# FCT_connector.net
KiCad netlist of a schematic drawn in Altium Designer
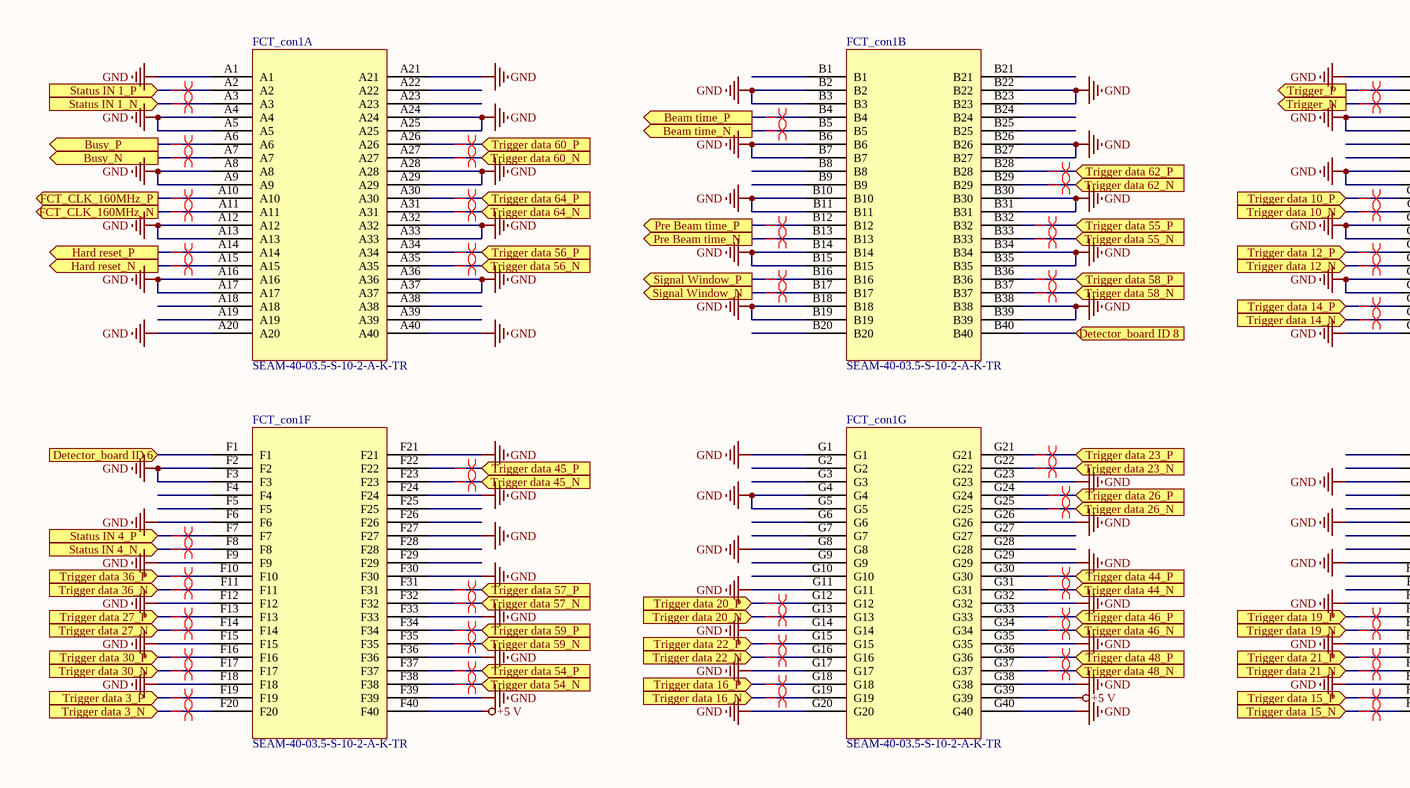
[diagram p0: FCT_connector.SchDoc, left]
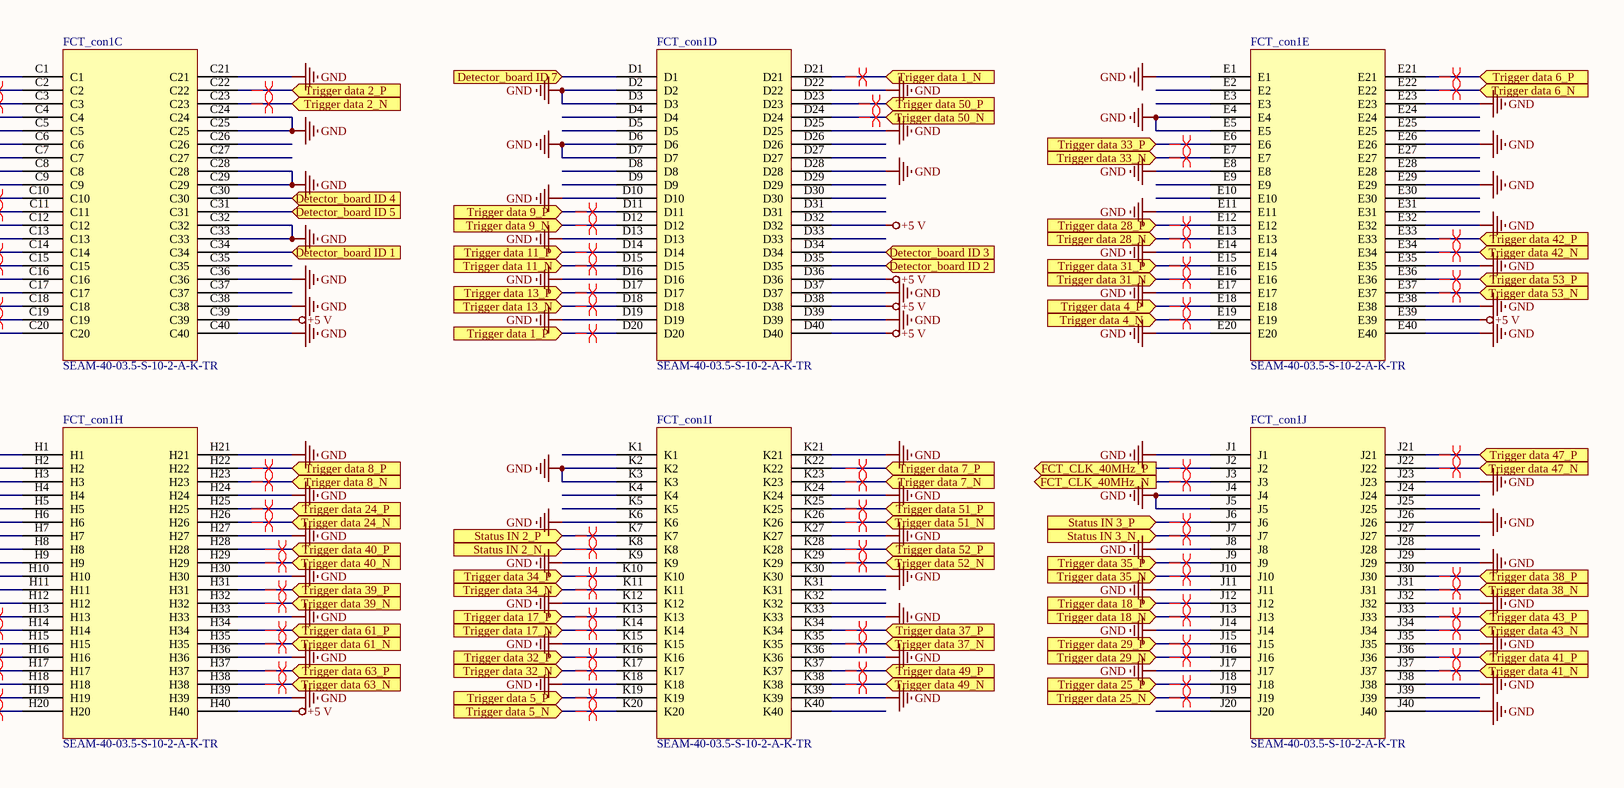
[diagram p1: FCT_connector.SchDoc, right]

(export (version "E")
  (design (tool "Eeschema 10.0.6"))
  (components
    (comp (ref "FCT_con1")
      (value "SEAM-40-03.5-S-10-2-A-K-TR")
      (footprint "SEAM-40-03.5-S-10-2-A-K-TR")
      (libsource (lib "vDevice") (part "SEAM-40-03.5-S-10-2-A-K-TR"))
    )
  )
  (nets
    (net (code "1") (name "+5 V") (class "Default")
      (node (ref "FCT_con1") (pin "C39") (pinfunction "C39_C39") (pintype "passive"))
      (node (ref "FCT_con1") (pin "D32") (pinfunction "D32_D32") (pintype "passive"))
      (node (ref "FCT_con1") (pin "D36") (pinfunction "D36_D36") (pintype "passive"))
      (node (ref "FCT_con1") (pin "D38") (pinfunction "D38_D38") (pintype "passive"))
      (node (ref "FCT_con1") (pin "D40") (pinfunction "D40_D40") (pintype "passive"))
      (node (ref "FCT_con1") (pin "E39") (pinfunction "E39_E39") (pintype "passive"))
      (node (ref "FCT_con1") (pin "F40") (pinfunction "F40_F40") (pintype "passive"))
      (node (ref "FCT_con1") (pin "G39") (pinfunction "G39_G39") (pintype "passive"))
      (node (ref "FCT_con1") (pin "H40") (pinfunction "H40_H40") (pintype "passive"))
    )
    (net (code "2") (name "/Beam time_N") (class "Default")
      (node (ref "FCT_con1") (pin "B5") (pinfunction "B5_B5") (pintype "passive"))
    )
    (net (code "3") (name "/Beam time_P") (class "Default")
      (node (ref "FCT_con1") (pin "B4") (pinfunction "B4_B4") (pintype "passive"))
    )
    (net (code "4") (name "/Busy_N") (class "Default")
      (node (ref "FCT_con1") (pin "A7") (pinfunction "A7_A7") (pintype "passive"))
    )
    (net (code "5") (name "/Busy_P") (class "Default")
      (node (ref "FCT_con1") (pin "A6") (pinfunction "A6_A6") (pintype "passive"))
    )
    (net (code "6") (name "/Detector_board ID 1") (class "Default")
      (node (ref "FCT_con1") (pin "C34") (pinfunction "C34_C34") (pintype "passive"))
    )
    (net (code "7") (name "/Detector_board ID 2") (class "Default")
      (node (ref "FCT_con1") (pin "D35") (pinfunction "D35_D35") (pintype "passive"))
    )
    (net (code "8") (name "/Detector_board ID 3") (class "Default")
      (node (ref "FCT_con1") (pin "D34") (pinfunction "D34_D34") (pintype "passive"))
    )
    (net (code "9") (name "/Detector_board ID 4") (class "Default")
      (node (ref "FCT_con1") (pin "C30") (pinfunction "C30_C30") (pintype "passive"))
    )
    (net (code "10") (name "/Detector_board ID 5") (class "Default")
      (node (ref "FCT_con1") (pin "C31") (pinfunction "C31_C31") (pintype "passive"))
    )
    (net (code "11") (name "/Detector_board ID 6") (class "Default")
      (node (ref "FCT_con1") (pin "F1") (pinfunction "F1_F1") (pintype "passive"))
    )
    (net (code "12") (name "/Detector_board ID 7") (class "Default")
      (node (ref "FCT_con1") (pin "D1") (pinfunction "D1_D1") (pintype "passive"))
    )
    (net (code "13") (name "/Detector_board ID 8") (class "Default")
      (node (ref "FCT_con1") (pin "B40") (pinfunction "B40_B40") (pintype "passive"))
    )
    (net (code "14") (name "/FCT_CLK_40MHz_N") (class "Default")
      (node (ref "FCT_con1") (pin "J3") (pinfunction "J3_J3") (pintype "passive"))
    )
    (net (code "15") (name "/FCT_CLK_40MHz_P") (class "Default")
      (node (ref "FCT_con1") (pin "J2") (pinfunction "J2_J2") (pintype "passive"))
    )
    (net (code "16") (name "/FCT_CLK_160MHz_N") (class "Default")
      (node (ref "FCT_con1") (pin "A11") (pinfunction "A11_A11") (pintype "passive"))
    )
    (net (code "17") (name "/FCT_CLK_160MHz_P") (class "Default")
      (node (ref "FCT_con1") (pin "A10") (pinfunction "A10_A10") (pintype "passive"))
    )
    (net (code "18") (name "/Hard reset_N") (class "Default")
      (node (ref "FCT_con1") (pin "A15") (pinfunction "A15_A15") (pintype "passive"))
    )
    (net (code "19") (name "/Hard reset_P") (class "Default")
      (node (ref "FCT_con1") (pin "A14") (pinfunction "A14_A14") (pintype "passive"))
    )
    (net (code "20") (name "/Pre Beam time_N") (class "Default")
      (node (ref "FCT_con1") (pin "B13") (pinfunction "B13_B13") (pintype "passive"))
    )
    (net (code "21") (name "/Pre Beam time_P") (class "Default")
      (node (ref "FCT_con1") (pin "B12") (pinfunction "B12_B12") (pintype "passive"))
    )
    (net (code "22") (name "/Signal Window_N") (class "Default")
      (node (ref "FCT_con1") (pin "B17") (pinfunction "B17_B17") (pintype "passive"))
    )
    (net (code "23") (name "/Signal Window_P") (class "Default")
      (node (ref "FCT_con1") (pin "B16") (pinfunction "B16_B16") (pintype "passive"))
    )
    (net (code "24") (name "/Status IN 1_N") (class "Default")
      (node (ref "FCT_con1") (pin "A3") (pinfunction "A3_A3") (pintype "passive"))
    )
    (net (code "25") (name "/Status IN 1_P") (class "Default")
      (node (ref "FCT_con1") (pin "A2") (pinfunction "A2_A2") (pintype "passive"))
    )
    (net (code "26") (name "/Status IN 2_N") (class "Default")
      (node (ref "FCT_con1") (pin "K8") (pinfunction "K8_K8") (pintype "passive"))
    )
    (net (code "27") (name "/Status IN 2_P") (class "Default")
      (node (ref "FCT_con1") (pin "K7") (pinfunction "K7_K7") (pintype "passive"))
    )
    (net (code "28") (name "/Status IN 3_N") (class "Default")
      (node (ref "FCT_con1") (pin "J7") (pinfunction "J7_J7") (pintype "passive"))
    )
    (net (code "29") (name "/Status IN 3_P") (class "Default")
      (node (ref "FCT_con1") (pin "J6") (pinfunction "J6_J6") (pintype "passive"))
    )
    (net (code "30") (name "/Status IN 4_N") (class "Default")
      (node (ref "FCT_con1") (pin "F8") (pinfunction "F8_F8") (pintype "passive"))
    )
    (net (code "31") (name "/Status IN 4_P") (class "Default")
      (node (ref "FCT_con1") (pin "F7") (pinfunction "F7_F7") (pintype "passive"))
    )
    (net (code "32") (name "/Trigger data 1_N") (class "Default")
      (node (ref "FCT_con1") (pin "D21") (pinfunction "D21_D21") (pintype "passive"))
    )
    (net (code "33") (name "/Trigger data 1_P") (class "Default")
      (node (ref "FCT_con1") (pin "D20") (pinfunction "D20_D20") (pintype "passive"))
    )
    (net (code "34") (name "/Trigger data 2_N") (class "Default")
      (node (ref "FCT_con1") (pin "C23") (pinfunction "C23_C23") (pintype "passive"))
    )
    (net (code "35") (name "/Trigger data 2_P") (class "Default")
      (node (ref "FCT_con1") (pin "C22") (pinfunction "C22_C22") (pintype "passive"))
    )
    (net (code "36") (name "/Trigger data 3_N") (class "Default")
      (node (ref "FCT_con1") (pin "F20") (pinfunction "F20_F20") (pintype "passive"))
    )
    (net (code "37") (name "/Trigger data 3_P") (class "Default")
      (node (ref "FCT_con1") (pin "F19") (pinfunction "F19_F19") (pintype "passive"))
    )
    (net (code "38") (name "/Trigger data 4_N") (class "Default")
      (node (ref "FCT_con1") (pin "E19") (pinfunction "E19_E19") (pintype "passive"))
    )
    (net (code "39") (name "/Trigger data 4_P") (class "Default")
      (node (ref "FCT_con1") (pin "E18") (pinfunction "E18_E18") (pintype "passive"))
    )
    (net (code "40") (name "/Trigger data 5_N") (class "Default")
      (node (ref "FCT_con1") (pin "K20") (pinfunction "K20_K20") (pintype "passive"))
    )
    (net (code "41") (name "/Trigger data 5_P") (class "Default")
      (node (ref "FCT_con1") (pin "K19") (pinfunction "K19_K19") (pintype "passive"))
    )
    (net (code "42") (name "/Trigger data 6_N") (class "Default")
      (node (ref "FCT_con1") (pin "E22") (pinfunction "E22_E22") (pintype "passive"))
    )
    (net (code "43") (name "/Trigger data 6_P") (class "Default")
      (node (ref "FCT_con1") (pin "E21") (pinfunction "E21_E21") (pintype "passive"))
    )
    (net (code "44") (name "/Trigger data 7_N") (class "Default")
      (node (ref "FCT_con1") (pin "K23") (pinfunction "K23_K23") (pintype "passive"))
    )
    (net (code "45") (name "/Trigger data 7_P") (class "Default")
      (node (ref "FCT_con1") (pin "K22") (pinfunction "K22_K22") (pintype "passive"))
    )
    (net (code "46") (name "/Trigger data 8_N") (class "Default")
      (node (ref "FCT_con1") (pin "H23") (pinfunction "H23_H23") (pintype "passive"))
    )
    (net (code "47") (name "/Trigger data 8_P") (class "Default")
      (node (ref "FCT_con1") (pin "H22") (pinfunction "H22_H22") (pintype "passive"))
    )
    (net (code "48") (name "/Trigger data 9_N") (class "Default")
      (node (ref "FCT_con1") (pin "D12") (pinfunction "D12_D12") (pintype "passive"))
    )
    (net (code "49") (name "/Trigger data 9_P") (class "Default")
      (node (ref "FCT_con1") (pin "D11") (pinfunction "D11_D11") (pintype "passive"))
    )
    (net (code "50") (name "/Trigger data 10_N") (class "Default")
      (node (ref "FCT_con1") (pin "C11") (pinfunction "C11_C11") (pintype "passive"))
    )
    (net (code "51") (name "/Trigger data 10_P") (class "Default")
      (node (ref "FCT_con1") (pin "C10") (pinfunction "C10_C10") (pintype "passive"))
    )
    (net (code "52") (name "/Trigger data 11_N") (class "Default")
      (node (ref "FCT_con1") (pin "D15") (pinfunction "D15_D15") (pintype "passive"))
    )
    (net (code "53") (name "/Trigger data 11_P") (class "Default")
      (node (ref "FCT_con1") (pin "D14") (pinfunction "D14_D14") (pintype "passive"))
    )
    (net (code "54") (name "/Trigger data 12_N") (class "Default")
      (node (ref "FCT_con1") (pin "C15") (pinfunction "C15_C15") (pintype "passive"))
    )
    (net (code "55") (name "/Trigger data 12_P") (class "Default")
      (node (ref "FCT_con1") (pin "C14") (pinfunction "C14_C14") (pintype "passive"))
    )
    (net (code "56") (name "/Trigger data 13_N") (class "Default")
      (node (ref "FCT_con1") (pin "D18") (pinfunction "D18_D18") (pintype "passive"))
    )
    (net (code "57") (name "/Trigger data 13_P") (class "Default")
      (node (ref "FCT_con1") (pin "D17") (pinfunction "D17_D17") (pintype "passive"))
    )
    (net (code "58") (name "/Trigger data 14_N") (class "Default")
      (node (ref "FCT_con1") (pin "C19") (pinfunction "C19_C19") (pintype "passive"))
    )
    (net (code "59") (name "/Trigger data 14_P") (class "Default")
      (node (ref "FCT_con1") (pin "C18") (pinfunction "C18_C18") (pintype "passive"))
    )
    (net (code "60") (name "/Trigger data 15_N") (class "Default")
      (node (ref "FCT_con1") (pin "H20") (pinfunction "H20_H20") (pintype "passive"))
    )
    (net (code "61") (name "/Trigger data 15_P") (class "Default")
      (node (ref "FCT_con1") (pin "H19") (pinfunction "H19_H19") (pintype "passive"))
    )
    (net (code "62") (name "/Trigger data 16_N") (class "Default")
      (node (ref "FCT_con1") (pin "G19") (pinfunction "G19_G19") (pintype "passive"))
    )
    (net (code "63") (name "/Trigger data 16_P") (class "Default")
      (node (ref "FCT_con1") (pin "G18") (pinfunction "G18_G18") (pintype "passive"))
    )
    (net (code "64") (name "/Trigger data 17_N") (class "Default")
      (node (ref "FCT_con1") (pin "K14") (pinfunction "K14_K14") (pintype "passive"))
    )
    (net (code "65") (name "/Trigger data 17_P") (class "Default")
      (node (ref "FCT_con1") (pin "K13") (pinfunction "K13_K13") (pintype "passive"))
    )
    (net (code "66") (name "/Trigger data 18_N") (class "Default")
      (node (ref "FCT_con1") (pin "J13") (pinfunction "J13_J13") (pintype "passive"))
    )
    (net (code "67") (name "/Trigger data 18_P") (class "Default")
      (node (ref "FCT_con1") (pin "J12") (pinfunction "J12_J12") (pintype "passive"))
    )
    (net (code "68") (name "/Trigger data 19_N") (class "Default")
      (node (ref "FCT_con1") (pin "H14") (pinfunction "H14_H14") (pintype "passive"))
    )
    (net (code "69") (name "/Trigger data 19_P") (class "Default")
      (node (ref "FCT_con1") (pin "H13") (pinfunction "H13_H13") (pintype "passive"))
    )
    (net (code "70") (name "/Trigger data 20_N") (class "Default")
      (node (ref "FCT_con1") (pin "G13") (pinfunction "G13_G13") (pintype "passive"))
    )
    (net (code "71") (name "/Trigger data 20_P") (class "Default")
      (node (ref "FCT_con1") (pin "G12") (pinfunction "G12_G12") (pintype "passive"))
    )
    (net (code "72") (name "/Trigger data 21_N") (class "Default")
      (node (ref "FCT_con1") (pin "H17") (pinfunction "H17_H17") (pintype "passive"))
    )
    (net (code "73") (name "/Trigger data 21_P") (class "Default")
      (node (ref "FCT_con1") (pin "H16") (pinfunction "H16_H16") (pintype "passive"))
    )
    (net (code "74") (name "/Trigger data 22_N") (class "Default")
      (node (ref "FCT_con1") (pin "G16") (pinfunction "G16_G16") (pintype "passive"))
    )
    (net (code "75") (name "/Trigger data 22_P") (class "Default")
      (node (ref "FCT_con1") (pin "G15") (pinfunction "G15_G15") (pintype "passive"))
    )
    (net (code "76") (name "/Trigger data 23_N") (class "Default")
      (node (ref "FCT_con1") (pin "G22") (pinfunction "G22_G22") (pintype "passive"))
    )
    (net (code "77") (name "/Trigger data 23_P") (class "Default")
      (node (ref "FCT_con1") (pin "G21") (pinfunction "G21_G21") (pintype "passive"))
    )
    (net (code "78") (name "/Trigger data 24_N") (class "Default")
      (node (ref "FCT_con1") (pin "H26") (pinfunction "H26_H26") (pintype "passive"))
    )
    (net (code "79") (name "/Trigger data 24_P") (class "Default")
      (node (ref "FCT_con1") (pin "H25") (pinfunction "H25_H25") (pintype "passive"))
    )
    (net (code "80") (name "/Trigger data 25_N") (class "Default")
      (node (ref "FCT_con1") (pin "J19") (pinfunction "J19_J19") (pintype "passive"))
    )
    (net (code "81") (name "/Trigger data 25_P") (class "Default")
      (node (ref "FCT_con1") (pin "J18") (pinfunction "J18_J18") (pintype "passive"))
    )
    (net (code "82") (name "/Trigger data 26_N") (class "Default")
      (node (ref "FCT_con1") (pin "G25") (pinfunction "G25_G25") (pintype "passive"))
    )
    (net (code "83") (name "/Trigger data 26_P") (class "Default")
      (node (ref "FCT_con1") (pin "G24") (pinfunction "G24_G24") (pintype "passive"))
    )
    (net (code "84") (name "/Trigger data 27_N") (class "Default")
      (node (ref "FCT_con1") (pin "F14") (pinfunction "F14_F14") (pintype "passive"))
    )
    (net (code "85") (name "/Trigger data 27_P") (class "Default")
      (node (ref "FCT_con1") (pin "F13") (pinfunction "F13_F13") (pintype "passive"))
    )
    (net (code "86") (name "/Trigger data 28_N") (class "Default")
      (node (ref "FCT_con1") (pin "E13") (pinfunction "E13_E13") (pintype "passive"))
    )
    (net (code "87") (name "/Trigger data 28_P") (class "Default")
      (node (ref "FCT_con1") (pin "E12") (pinfunction "E12_E12") (pintype "passive"))
    )
    (net (code "88") (name "/Trigger data 29_N") (class "Default")
      (node (ref "FCT_con1") (pin "J16") (pinfunction "J16_J16") (pintype "passive"))
    )
    (net (code "89") (name "/Trigger data 29_P") (class "Default")
      (node (ref "FCT_con1") (pin "J15") (pinfunction "J15_J15") (pintype "passive"))
    )
    (net (code "90") (name "/Trigger data 30_N") (class "Default")
      (node (ref "FCT_con1") (pin "F17") (pinfunction "F17_F17") (pintype "passive"))
    )
    (net (code "91") (name "/Trigger data 30_P") (class "Default")
      (node (ref "FCT_con1") (pin "F16") (pinfunction "F16_F16") (pintype "passive"))
    )
    (net (code "92") (name "/Trigger data 31_N") (class "Default")
      (node (ref "FCT_con1") (pin "E16") (pinfunction "E16_E16") (pintype "passive"))
    )
    (net (code "93") (name "/Trigger data 31_P") (class "Default")
      (node (ref "FCT_con1") (pin "E15") (pinfunction "E15_E15") (pintype "passive"))
    )
    (net (code "94") (name "/Trigger data 32_N") (class "Default")
      (node (ref "FCT_con1") (pin "K17") (pinfunction "K17_K17") (pintype "passive"))
    )
    (net (code "95") (name "/Trigger data 32_P") (class "Default")
      (node (ref "FCT_con1") (pin "K16") (pinfunction "K16_K16") (pintype "passive"))
    )
    (net (code "96") (name "/Trigger data 33_N") (class "Default")
      (node (ref "FCT_con1") (pin "E7") (pinfunction "E7_E7") (pintype "passive"))
    )
    (net (code "97") (name "/Trigger data 33_P") (class "Default")
      (node (ref "FCT_con1") (pin "E6") (pinfunction "E6_E6") (pintype "passive"))
    )
    (net (code "98") (name "/Trigger data 34_N") (class "Default")
      (node (ref "FCT_con1") (pin "K11") (pinfunction "K11_K11") (pintype "passive"))
    )
    (net (code "99") (name "/Trigger data 34_P") (class "Default")
      (node (ref "FCT_con1") (pin "K10") (pinfunction "K10_K10") (pintype "passive"))
    )
    (net (code "100") (name "/Trigger data 35_N") (class "Default")
      (node (ref "FCT_con1") (pin "J10") (pinfunction "J10_J10") (pintype "passive"))
    )
    (net (code "101") (name "/Trigger data 35_P") (class "Default")
      (node (ref "FCT_con1") (pin "J9") (pinfunction "J9_J9") (pintype "passive"))
    )
    (net (code "102") (name "/Trigger data 36_N") (class "Default")
      (node (ref "FCT_con1") (pin "F11") (pinfunction "F11_F11") (pintype "passive"))
    )
    (net (code "103") (name "/Trigger data 36_P") (class "Default")
      (node (ref "FCT_con1") (pin "F10") (pinfunction "F10_F10") (pintype "passive"))
    )
    (net (code "104") (name "/Trigger data 37_N") (class "Default")
      (node (ref "FCT_con1") (pin "K35") (pinfunction "K35_K35") (pintype "passive"))
    )
    (net (code "105") (name "/Trigger data 37_P") (class "Default")
      (node (ref "FCT_con1") (pin "K34") (pinfunction "K34_K34") (pintype "passive"))
    )
    (net (code "106") (name "/Trigger data 38_N") (class "Default")
      (node (ref "FCT_con1") (pin "J31") (pinfunction "J31_J31") (pintype "passive"))
    )
    (net (code "107") (name "/Trigger data 38_P") (class "Default")
      (node (ref "FCT_con1") (pin "J30") (pinfunction "J30_J30") (pintype "passive"))
    )
    (net (code "108") (name "/Trigger data 39_N") (class "Default")
      (node (ref "FCT_con1") (pin "H32") (pinfunction "H32_H32") (pintype "passive"))
    )
    (net (code "109") (name "/Trigger data 39_P") (class "Default")
      (node (ref "FCT_con1") (pin "H31") (pinfunction "H31_H31") (pintype "passive"))
    )
    (net (code "110") (name "/Trigger data 40_N") (class "Default")
      (node (ref "FCT_con1") (pin "H29") (pinfunction "H29_H29") (pintype "passive"))
    )
    (net (code "111") (name "/Trigger data 40_P") (class "Default")
      (node (ref "FCT_con1") (pin "H28") (pinfunction "H28_H28") (pintype "passive"))
    )
    (net (code "112") (name "/Trigger data 41_N") (class "Default")
      (node (ref "FCT_con1") (pin "J37") (pinfunction "J37_J37") (pintype "passive"))
    )
    (net (code "113") (name "/Trigger data 41_P") (class "Default")
      (node (ref "FCT_con1") (pin "J36") (pinfunction "J36_J36") (pintype "passive"))
    )
    (net (code "114") (name "/Trigger data 42_N") (class "Default")
      (node (ref "FCT_con1") (pin "E34") (pinfunction "E34_E34") (pintype "passive"))
    )
    (net (code "115") (name "/Trigger data 42_P") (class "Default")
      (node (ref "FCT_con1") (pin "E33") (pinfunction "E33_E33") (pintype "passive"))
    )
    (net (code "116") (name "/Trigger data 43_N") (class "Default")
      (node (ref "FCT_con1") (pin "J34") (pinfunction "J34_J34") (pintype "passive"))
    )
    (net (code "117") (name "/Trigger data 43_P") (class "Default")
      (node (ref "FCT_con1") (pin "J33") (pinfunction "J33_J33") (pintype "passive"))
    )
    (net (code "118") (name "/Trigger data 44_N") (class "Default")
      (node (ref "FCT_con1") (pin "G31") (pinfunction "G31_G31") (pintype "passive"))
    )
    (net (code "119") (name "/Trigger data 44_P") (class "Default")
      (node (ref "FCT_con1") (pin "G30") (pinfunction "G30_G30") (pintype "passive"))
    )
    (net (code "120") (name "/Trigger data 45_N") (class "Default")
      (node (ref "FCT_con1") (pin "F23") (pinfunction "F23_F23") (pintype "passive"))
    )
    (net (code "121") (name "/Trigger data 45_P") (class "Default")
      (node (ref "FCT_con1") (pin "F22") (pinfunction "F22_F22") (pintype "passive"))
    )
    (net (code "122") (name "/Trigger data 46_N") (class "Default")
      (node (ref "FCT_con1") (pin "G34") (pinfunction "G34_G34") (pintype "passive"))
    )
    (net (code "123") (name "/Trigger data 46_P") (class "Default")
      (node (ref "FCT_con1") (pin "G33") (pinfunction "G33_G33") (pintype "passive"))
    )
    (net (code "124") (name "/Trigger data 47_N") (class "Default")
      (node (ref "FCT_con1") (pin "J22") (pinfunction "J22_J22") (pintype "passive"))
    )
    (net (code "125") (name "/Trigger data 47_P") (class "Default")
      (node (ref "FCT_con1") (pin "J21") (pinfunction "J21_J21") (pintype "passive"))
    )
    (net (code "126") (name "/Trigger data 48_N") (class "Default")
      (node (ref "FCT_con1") (pin "G37") (pinfunction "G37_G37") (pintype "passive"))
    )
    (net (code "127") (name "/Trigger data 48_P") (class "Default")
      (node (ref "FCT_con1") (pin "G36") (pinfunction "G36_G36") (pintype "passive"))
    )
    (net (code "128") (name "/Trigger data 49_N") (class "Default")
      (node (ref "FCT_con1") (pin "K38") (pinfunction "K38_K38") (pintype "passive"))
    )
    (net (code "129") (name "/Trigger data 49_P") (class "Default")
      (node (ref "FCT_con1") (pin "K37") (pinfunction "K37_K37") (pintype "passive"))
    )
    (net (code "130") (name "/Trigger data 50_N") (class "Default")
      (node (ref "FCT_con1") (pin "D24") (pinfunction "D24_D24") (pintype "passive"))
    )
    (net (code "131") (name "/Trigger data 50_P") (class "Default")
      (node (ref "FCT_con1") (pin "D23") (pinfunction "D23_D23") (pintype "passive"))
    )
    (net (code "132") (name "/Trigger data 51_N") (class "Default")
      (node (ref "FCT_con1") (pin "K26") (pinfunction "K26_K26") (pintype "passive"))
    )
    (net (code "133") (name "/Trigger data 51_P") (class "Default")
      (node (ref "FCT_con1") (pin "K25") (pinfunction "K25_K25") (pintype "passive"))
    )
    (net (code "134") (name "/Trigger data 52_N") (class "Default")
      (node (ref "FCT_con1") (pin "K29") (pinfunction "K29_K29") (pintype "passive"))
    )
    (net (code "135") (name "/Trigger data 52_P") (class "Default")
      (node (ref "FCT_con1") (pin "K28") (pinfunction "K28_K28") (pintype "passive"))
    )
    (net (code "136") (name "/Trigger data 53_N") (class "Default")
      (node (ref "FCT_con1") (pin "E37") (pinfunction "E37_E37") (pintype "passive"))
    )
    (net (code "137") (name "/Trigger data 53_P") (class "Default")
      (node (ref "FCT_con1") (pin "E36") (pinfunction "E36_E36") (pintype "passive"))
    )
    (net (code "138") (name "/Trigger data 54_N") (class "Default")
      (node (ref "FCT_con1") (pin "F38") (pinfunction "F38_F38") (pintype "passive"))
    )
    (net (code "139") (name "/Trigger data 54_P") (class "Default")
      (node (ref "FCT_con1") (pin "F37") (pinfunction "F37_F37") (pintype "passive"))
    )
    (net (code "140") (name "/Trigger data 55_N") (class "Default")
      (node (ref "FCT_con1") (pin "B33") (pinfunction "B33_B33") (pintype "passive"))
    )
    (net (code "141") (name "/Trigger data 55_P") (class "Default")
      (node (ref "FCT_con1") (pin "B32") (pinfunction "B32_B32") (pintype "passive"))
    )
    (net (code "142") (name "/Trigger data 56_N") (class "Default")
      (node (ref "FCT_con1") (pin "A35") (pinfunction "A35_A35") (pintype "passive"))
    )
    (net (code "143") (name "/Trigger data 56_P") (class "Default")
      (node (ref "FCT_con1") (pin "A34") (pinfunction "A34_A34") (pintype "passive"))
    )
    (net (code "144") (name "/Trigger data 57_N") (class "Default")
      (node (ref "FCT_con1") (pin "F32") (pinfunction "F32_F32") (pintype "passive"))
    )
    (net (code "145") (name "/Trigger data 57_P") (class "Default")
      (node (ref "FCT_con1") (pin "F31") (pinfunction "F31_F31") (pintype "passive"))
    )
    (net (code "146") (name "/Trigger data 58_N") (class "Default")
      (node (ref "FCT_con1") (pin "B37") (pinfunction "B37_B37") (pintype "passive"))
    )
    (net (code "147") (name "/Trigger data 58_P") (class "Default")
      (node (ref "FCT_con1") (pin "B36") (pinfunction "B36_B36") (pintype "passive"))
    )
    (net (code "148") (name "/Trigger data 59_N") (class "Default")
      (node (ref "FCT_con1") (pin "F35") (pinfunction "F35_F35") (pintype "passive"))
    )
    (net (code "149") (name "/Trigger data 59_P") (class "Default")
      (node (ref "FCT_con1") (pin "F34") (pinfunction "F34_F34") (pintype "passive"))
    )
    (net (code "150") (name "/Trigger data 60_N") (class "Default")
      (node (ref "FCT_con1") (pin "A27") (pinfunction "A27_A27") (pintype "passive"))
    )
    (net (code "151") (name "/Trigger data 60_P") (class "Default")
      (node (ref "FCT_con1") (pin "A26") (pinfunction "A26_A26") (pintype "passive"))
    )
    (net (code "152") (name "/Trigger data 61_N") (class "Default")
      (node (ref "FCT_con1") (pin "H35") (pinfunction "H35_H35") (pintype "passive"))
    )
    (net (code "153") (name "/Trigger data 61_P") (class "Default")
      (node (ref "FCT_con1") (pin "H34") (pinfunction "H34_H34") (pintype "passive"))
    )
    (net (code "154") (name "/Trigger data 62_N") (class "Default")
      (node (ref "FCT_con1") (pin "B29") (pinfunction "B29_B29") (pintype "passive"))
    )
    (net (code "155") (name "/Trigger data 62_P") (class "Default")
      (node (ref "FCT_con1") (pin "B28") (pinfunction "B28_B28") (pintype "passive"))
    )
    (net (code "156") (name "/Trigger data 63_N") (class "Default")
      (node (ref "FCT_con1") (pin "H38") (pinfunction "H38_H38") (pintype "passive"))
    )
    (net (code "157") (name "/Trigger data 63_P") (class "Default")
      (node (ref "FCT_con1") (pin "H37") (pinfunction "H37_H37") (pintype "passive"))
    )
    (net (code "158") (name "/Trigger data 64_N") (class "Default")
      (node (ref "FCT_con1") (pin "A31") (pinfunction "A31_A31") (pintype "passive"))
    )
    (net (code "159") (name "/Trigger data 64_P") (class "Default")
      (node (ref "FCT_con1") (pin "A30") (pinfunction "A30_A30") (pintype "passive"))
    )
    (net (code "160") (name "/Trigger_N") (class "Default")
      (node (ref "FCT_con1") (pin "C3") (pinfunction "C3_C3") (pintype "passive"))
    )
    (net (code "161") (name "/Trigger_P") (class "Default")
      (node (ref "FCT_con1") (pin "C2") (pinfunction "C2_C2") (pintype "passive"))
    )
    (net (code "162") (name "GND") (class "Default")
      (node (ref "FCT_con1") (pin "A1") (pinfunction "A1_A1") (pintype "passive"))
      (node (ref "FCT_con1") (pin "A12") (pinfunction "A12_A12") (pintype "passive"))
      (node (ref "FCT_con1") (pin "A13") (pinfunction "A13_A13") (pintype "passive"))
      (node (ref "FCT_con1") (pin "A16") (pinfunction "A16_A16") (pintype "passive"))
      (node (ref "FCT_con1") (pin "A17") (pinfunction "A17_A17") (pintype "passive"))
      (node (ref "FCT_con1") (pin "A20") (pinfunction "A20_A20") (pintype "passive"))
      (node (ref "FCT_con1") (pin "A21") (pinfunction "A21_A21") (pintype "passive"))
      (node (ref "FCT_con1") (pin "A24") (pinfunction "A24_A24") (pintype "passive"))
      (node (ref "FCT_con1") (pin "A25") (pinfunction "A25_A25") (pintype "passive"))
      (node (ref "FCT_con1") (pin "A28") (pinfunction "A28_A28") (pintype "passive"))
      (node (ref "FCT_con1") (pin "A29") (pinfunction "A29_A29") (pintype "passive"))
      (node (ref "FCT_con1") (pin "A32") (pinfunction "A32_A32") (pintype "passive"))
      (node (ref "FCT_con1") (pin "A33") (pinfunction "A33_A33") (pintype "passive"))
      (node (ref "FCT_con1") (pin "A36") (pinfunction "A36_A36") (pintype "passive"))
      (node (ref "FCT_con1") (pin "A37") (pinfunction "A37_A37") (pintype "passive"))
      (node (ref "FCT_con1") (pin "A4") (pinfunction "A4_A4") (pintype "passive"))
      (node (ref "FCT_con1") (pin "A40") (pinfunction "A40_A40") (pintype "passive"))
      (node (ref "FCT_con1") (pin "A5") (pinfunction "A5_A5") (pintype "passive"))
      (node (ref "FCT_con1") (pin "A8") (pinfunction "A8_A8") (pintype "passive"))
      (node (ref "FCT_con1") (pin "A9") (pinfunction "A9_A9") (pintype "passive"))
      (node (ref "FCT_con1") (pin "B10") (pinfunction "B10_B10") (pintype "passive"))
      (node (ref "FCT_con1") (pin "B11") (pinfunction "B11_B11") (pintype "passive"))
      (node (ref "FCT_con1") (pin "B14") (pinfunction "B14_B14") (pintype "passive"))
      (node (ref "FCT_con1") (pin "B15") (pinfunction "B15_B15") (pintype "passive"))
      (node (ref "FCT_con1") (pin "B18") (pinfunction "B18_B18") (pintype "passive"))
      (node (ref "FCT_con1") (pin "B19") (pinfunction "B19_B19") (pintype "passive"))
      (node (ref "FCT_con1") (pin "B2") (pinfunction "B2_B2") (pintype "passive"))
      (node (ref "FCT_con1") (pin "B22") (pinfunction "B22_B22") (pintype "passive"))
      (node (ref "FCT_con1") (pin "B23") (pinfunction "B23_B23") (pintype "passive"))
      (node (ref "FCT_con1") (pin "B26") (pinfunction "B26_B26") (pintype "passive"))
      (node (ref "FCT_con1") (pin "B27") (pinfunction "B27_B27") (pintype "passive"))
      (node (ref "FCT_con1") (pin "B3") (pinfunction "B3_B3") (pintype "passive"))
      (node (ref "FCT_con1") (pin "B30") (pinfunction "B30_B30") (pintype "passive"))
      (node (ref "FCT_con1") (pin "B31") (pinfunction "B31_B31") (pintype "passive"))
      (node (ref "FCT_con1") (pin "B34") (pinfunction "B34_B34") (pintype "passive"))
      (node (ref "FCT_con1") (pin "B35") (pinfunction "B35_B35") (pintype "passive"))
      (node (ref "FCT_con1") (pin "B38") (pinfunction "B38_B38") (pintype "passive"))
      (node (ref "FCT_con1") (pin "B39") (pinfunction "B39_B39") (pintype "passive"))
      (node (ref "FCT_con1") (pin "B6") (pinfunction "B6_B6") (pintype "passive"))
      (node (ref "FCT_con1") (pin "B7") (pinfunction "B7_B7") (pintype "passive"))
      (node (ref "FCT_con1") (pin "C1") (pinfunction "C1_C1") (pintype "passive"))
      (node (ref "FCT_con1") (pin "C12") (pinfunction "C12_C12") (pintype "passive"))
      (node (ref "FCT_con1") (pin "C13") (pinfunction "C13_C13") (pintype "passive"))
      (node (ref "FCT_con1") (pin "C16") (pinfunction "C16_C16") (pintype "passive"))
      (node (ref "FCT_con1") (pin "C17") (pinfunction "C17_C17") (pintype "passive"))
      (node (ref "FCT_con1") (pin "C20") (pinfunction "C20_C20") (pintype "passive"))
      (node (ref "FCT_con1") (pin "C21") (pinfunction "C21_C21") (pintype "passive"))
      (node (ref "FCT_con1") (pin "C24") (pinfunction "C24_C24") (pintype "passive"))
      (node (ref "FCT_con1") (pin "C25") (pinfunction "C25_C25") (pintype "passive"))
      (node (ref "FCT_con1") (pin "C28") (pinfunction "C28_C28") (pintype "passive"))
      (node (ref "FCT_con1") (pin "C29") (pinfunction "C29_C29") (pintype "passive"))
      (node (ref "FCT_con1") (pin "C32") (pinfunction "C32_C32") (pintype "passive"))
      (node (ref "FCT_con1") (pin "C33") (pinfunction "C33_C33") (pintype "passive"))
      (node (ref "FCT_con1") (pin "C36") (pinfunction "C36_C36") (pintype "passive"))
      (node (ref "FCT_con1") (pin "C38") (pinfunction "C38_C38") (pintype "passive"))
      (node (ref "FCT_con1") (pin "C4") (pinfunction "C4_C4") (pintype "passive"))
      (node (ref "FCT_con1") (pin "C40") (pinfunction "C40_C40") (pintype "passive"))
      (node (ref "FCT_con1") (pin "C5") (pinfunction "C5_C5") (pintype "passive"))
      (node (ref "FCT_con1") (pin "C8") (pinfunction "C8_C8") (pintype "passive"))
      (node (ref "FCT_con1") (pin "C9") (pinfunction "C9_C9") (pintype "passive"))
      (node (ref "FCT_con1") (pin "D10") (pinfunction "D10_D10") (pintype "passive"))
      (node (ref "FCT_con1") (pin "D13") (pinfunction "D13_D13") (pintype "passive"))
      (node (ref "FCT_con1") (pin "D16") (pinfunction "D16_D16") (pintype "passive"))
      (node (ref "FCT_con1") (pin "D19") (pinfunction "D19_D19") (pintype "passive"))
      (node (ref "FCT_con1") (pin "D2") (pinfunction "D2_D2") (pintype "passive"))
      (node (ref "FCT_con1") (pin "D22") (pinfunction "D22_D22") (pintype "passive"))
      (node (ref "FCT_con1") (pin "D25") (pinfunction "D25_D25") (pintype "passive"))
      (node (ref "FCT_con1") (pin "D28") (pinfunction "D28_D28") (pintype "passive"))
      (node (ref "FCT_con1") (pin "D3") (pinfunction "D3_D3") (pintype "passive"))
      (node (ref "FCT_con1") (pin "D37") (pinfunction "D37_D37") (pintype "passive"))
      (node (ref "FCT_con1") (pin "D39") (pinfunction "D39_D39") (pintype "passive"))
      (node (ref "FCT_con1") (pin "D6") (pinfunction "D6_D6") (pintype "passive"))
      (node (ref "FCT_con1") (pin "D7") (pinfunction "D7_D7") (pintype "passive"))
      (node (ref "FCT_con1") (pin "E1") (pinfunction "E1_E1") (pintype "passive"))
      (node (ref "FCT_con1") (pin "E11") (pinfunction "E11_E11") (pintype "passive"))
      (node (ref "FCT_con1") (pin "E14") (pinfunction "E14_E14") (pintype "passive"))
      (node (ref "FCT_con1") (pin "E17") (pinfunction "E17_E17") (pintype "passive"))
      (node (ref "FCT_con1") (pin "E20") (pinfunction "E20_E20") (pintype "passive"))
      (node (ref "FCT_con1") (pin "E23") (pinfunction "E23_E23") (pintype "passive"))
      (node (ref "FCT_con1") (pin "E26") (pinfunction "E26_E26") (pintype "passive"))
      (node (ref "FCT_con1") (pin "E29") (pinfunction "E29_E29") (pintype "passive"))
      (node (ref "FCT_con1") (pin "E32") (pinfunction "E32_E32") (pintype "passive"))
      (node (ref "FCT_con1") (pin "E35") (pinfunction "E35_E35") (pintype "passive"))
      (node (ref "FCT_con1") (pin "E38") (pinfunction "E38_E38") (pintype "passive"))
      (node (ref "FCT_con1") (pin "E4") (pinfunction "E4_E4") (pintype "passive"))
      (node (ref "FCT_con1") (pin "E40") (pinfunction "E40_E40") (pintype "passive"))
      (node (ref "FCT_con1") (pin "E5") (pinfunction "E5_E5") (pintype "passive"))
      (node (ref "FCT_con1") (pin "E8") (pinfunction "E8_E8") (pintype "passive"))
      (node (ref "FCT_con1") (pin "F12") (pinfunction "F12_F12") (pintype "passive"))
      (node (ref "FCT_con1") (pin "F15") (pinfunction "F15_F15") (pintype "passive"))
      (node (ref "FCT_con1") (pin "F18") (pinfunction "F18_F18") (pintype "passive"))
      (node (ref "FCT_con1") (pin "F2") (pinfunction "F2_F2") (pintype "passive"))
      (node (ref "FCT_con1") (pin "F21") (pinfunction "F21_F21") (pintype "passive"))
      (node (ref "FCT_con1") (pin "F24") (pinfunction "F24_F24") (pintype "passive"))
      (node (ref "FCT_con1") (pin "F27") (pinfunction "F27_F27") (pintype "passive"))
      (node (ref "FCT_con1") (pin "F3") (pinfunction "F3_F3") (pintype "passive"))
      (node (ref "FCT_con1") (pin "F30") (pinfunction "F30_F30") (pintype "passive"))
      (node (ref "FCT_con1") (pin "F33") (pinfunction "F33_F33") (pintype "passive"))
      (node (ref "FCT_con1") (pin "F36") (pinfunction "F36_F36") (pintype "passive"))
      (node (ref "FCT_con1") (pin "F39") (pinfunction "F39_F39") (pintype "passive"))
      (node (ref "FCT_con1") (pin "F6") (pinfunction "F6_F6") (pintype "passive"))
      (node (ref "FCT_con1") (pin "F9") (pinfunction "F9_F9") (pintype "passive"))
      (node (ref "FCT_con1") (pin "G1") (pinfunction "G1_G1") (pintype "passive"))
      (node (ref "FCT_con1") (pin "G11") (pinfunction "G11_G11") (pintype "passive"))
      (node (ref "FCT_con1") (pin "G14") (pinfunction "G14_G14") (pintype "passive"))
      (node (ref "FCT_con1") (pin "G17") (pinfunction "G17_G17") (pintype "passive"))
      (node (ref "FCT_con1") (pin "G20") (pinfunction "G20_G20") (pintype "passive"))
      (node (ref "FCT_con1") (pin "G23") (pinfunction "G23_G23") (pintype "passive"))
      (node (ref "FCT_con1") (pin "G26") (pinfunction "G26_G26") (pintype "passive"))
      (node (ref "FCT_con1") (pin "G29") (pinfunction "G29_G29") (pintype "passive"))
      (node (ref "FCT_con1") (pin "G32") (pinfunction "G32_G32") (pintype "passive"))
      (node (ref "FCT_con1") (pin "G35") (pinfunction "G35_G35") (pintype "passive"))
      (node (ref "FCT_con1") (pin "G38") (pinfunction "G38_G38") (pintype "passive"))
      (node (ref "FCT_con1") (pin "G4") (pinfunction "G4_G4") (pintype "passive"))
      (node (ref "FCT_con1") (pin "G40") (pinfunction "G40_G40") (pintype "passive"))
      (node (ref "FCT_con1") (pin "G5") (pinfunction "G5_G5") (pintype "passive"))
      (node (ref "FCT_con1") (pin "G8") (pinfunction "G8_G8") (pintype "passive"))
      (node (ref "FCT_con1") (pin "H12") (pinfunction "H12_H12") (pintype "passive"))
      (node (ref "FCT_con1") (pin "H15") (pinfunction "H15_H15") (pintype "passive"))
      (node (ref "FCT_con1") (pin "H18") (pinfunction "H18_H18") (pintype "passive"))
      (node (ref "FCT_con1") (pin "H21") (pinfunction "H21_H21") (pintype "passive"))
      (node (ref "FCT_con1") (pin "H24") (pinfunction "H24_H24") (pintype "passive"))
      (node (ref "FCT_con1") (pin "H27") (pinfunction "H27_H27") (pintype "passive"))
      (node (ref "FCT_con1") (pin "H3") (pinfunction "H3_H3") (pintype "passive"))
      (node (ref "FCT_con1") (pin "H30") (pinfunction "H30_H30") (pintype "passive"))
      (node (ref "FCT_con1") (pin "H33") (pinfunction "H33_H33") (pintype "passive"))
      (node (ref "FCT_con1") (pin "H36") (pinfunction "H36_H36") (pintype "passive"))
      (node (ref "FCT_con1") (pin "H39") (pinfunction "H39_H39") (pintype "passive"))
      (node (ref "FCT_con1") (pin "H6") (pinfunction "H6_H6") (pintype "passive"))
      (node (ref "FCT_con1") (pin "H9") (pinfunction "H9_H9") (pintype "passive"))
      (node (ref "FCT_con1") (pin "J1") (pinfunction "J1_J1") (pintype "passive"))
      (node (ref "FCT_con1") (pin "J11") (pinfunction "J11_J11") (pintype "passive"))
      (node (ref "FCT_con1") (pin "J14") (pinfunction "J14_J14") (pintype "passive"))
      (node (ref "FCT_con1") (pin "J17") (pinfunction "J17_J17") (pintype "passive"))
      (node (ref "FCT_con1") (pin "J23") (pinfunction "J23_J23") (pintype "passive"))
      (node (ref "FCT_con1") (pin "J26") (pinfunction "J26_J26") (pintype "passive"))
      (node (ref "FCT_con1") (pin "J29") (pinfunction "J29_J29") (pintype "passive"))
      (node (ref "FCT_con1") (pin "J32") (pinfunction "J32_J32") (pintype "passive"))
      (node (ref "FCT_con1") (pin "J35") (pinfunction "J35_J35") (pintype "passive"))
      (node (ref "FCT_con1") (pin "J38") (pinfunction "J38_J38") (pintype "passive"))
      (node (ref "FCT_con1") (pin "J4") (pinfunction "J4_J4") (pintype "passive"))
      (node (ref "FCT_con1") (pin "J40") (pinfunction "J40_J40") (pintype "passive"))
      (node (ref "FCT_con1") (pin "J5") (pinfunction "J5_J5") (pintype "passive"))
      (node (ref "FCT_con1") (pin "J8") (pinfunction "J8_J8") (pintype "passive"))
      (node (ref "FCT_con1") (pin "K12") (pinfunction "K12_K12") (pintype "passive"))
      (node (ref "FCT_con1") (pin "K15") (pinfunction "K15_K15") (pintype "passive"))
      (node (ref "FCT_con1") (pin "K18") (pinfunction "K18_K18") (pintype "passive"))
      (node (ref "FCT_con1") (pin "K2") (pinfunction "K2_K2") (pintype "passive"))
      (node (ref "FCT_con1") (pin "K21") (pinfunction "K21_K21") (pintype "passive"))
      (node (ref "FCT_con1") (pin "K24") (pinfunction "K24_K24") (pintype "passive"))
      (node (ref "FCT_con1") (pin "K27") (pinfunction "K27_K27") (pintype "passive"))
      (node (ref "FCT_con1") (pin "K3") (pinfunction "K3_K3") (pintype "passive"))
      (node (ref "FCT_con1") (pin "K30") (pinfunction "K30_K30") (pintype "passive"))
      (node (ref "FCT_con1") (pin "K33") (pinfunction "K33_K33") (pintype "passive"))
      (node (ref "FCT_con1") (pin "K36") (pinfunction "K36_K36") (pintype "passive"))
      (node (ref "FCT_con1") (pin "K39") (pinfunction "K39_K39") (pintype "passive"))
      (node (ref "FCT_con1") (pin "K6") (pinfunction "K6_K6") (pintype "passive"))
      (node (ref "FCT_con1") (pin "K9") (pinfunction "K9_K9") (pintype "passive"))
    )
    (net (code "163") (name "unconnected-(FCT_con1-PadA18)") (class "Default")
      (node (ref "FCT_con1") (pin "A18") (pinfunction "A18_A18") (pintype "passive"))
    )
    (net (code "164") (name "unconnected-(FCT_con1-PadA19)") (class "Default")
      (node (ref "FCT_con1") (pin "A19") (pinfunction "A19_A19") (pintype "passive"))
    )
    (net (code "165") (name "unconnected-(FCT_con1-PadA22)") (class "Default")
      (node (ref "FCT_con1") (pin "A22") (pinfunction "A22_A22") (pintype "passive"))
    )
    (net (code "166") (name "unconnected-(FCT_con1-PadA23)") (class "Default")
      (node (ref "FCT_con1") (pin "A23") (pinfunction "A23_A23") (pintype "passive"))
    )
    (net (code "167") (name "unconnected-(FCT_con1-PadA38)") (class "Default")
      (node (ref "FCT_con1") (pin "A38") (pinfunction "A38_A38") (pintype "passive"))
    )
    (net (code "168") (name "unconnected-(FCT_con1-PadA39)") (class "Default")
      (node (ref "FCT_con1") (pin "A39") (pinfunction "A39_A39") (pintype "passive"))
    )
    (net (code "169") (name "unconnected-(FCT_con1-PadB1)") (class "Default")
      (node (ref "FCT_con1") (pin "B1") (pinfunction "B1_B1") (pintype "passive"))
    )
    (net (code "170") (name "unconnected-(FCT_con1-PadB8)") (class "Default")
      (node (ref "FCT_con1") (pin "B8") (pinfunction "B8_B8") (pintype "passive"))
    )
    (net (code "171") (name "unconnected-(FCT_con1-PadB9)") (class "Default")
      (node (ref "FCT_con1") (pin "B9") (pinfunction "B9_B9") (pintype "passive"))
    )
    (net (code "172") (name "unconnected-(FCT_con1-PadB20)") (class "Default")
      (node (ref "FCT_con1") (pin "B20") (pinfunction "B20_B20") (pintype "passive"))
    )
    (net (code "173") (name "unconnected-(FCT_con1-PadB21)") (class "Default")
      (node (ref "FCT_con1") (pin "B21") (pinfunction "B21_B21") (pintype "passive"))
    )
    (net (code "174") (name "unconnected-(FCT_con1-PadB24)") (class "Default")
      (node (ref "FCT_con1") (pin "B24") (pinfunction "B24_B24") (pintype "passive"))
    )
    (net (code "175") (name "unconnected-(FCT_con1-PadB25)") (class "Default")
      (node (ref "FCT_con1") (pin "B25") (pinfunction "B25_B25") (pintype "passive"))
    )
    (net (code "176") (name "unconnected-(FCT_con1-PadC6)") (class "Default")
      (node (ref "FCT_con1") (pin "C6") (pinfunction "C6_C6") (pintype "passive"))
    )
    (net (code "177") (name "unconnected-(FCT_con1-PadC7)") (class "Default")
      (node (ref "FCT_con1") (pin "C7") (pinfunction "C7_C7") (pintype "passive"))
    )
    (net (code "178") (name "unconnected-(FCT_con1-PadC26)") (class "Default")
      (node (ref "FCT_con1") (pin "C26") (pinfunction "C26_C26") (pintype "passive"))
    )
    (net (code "179") (name "unconnected-(FCT_con1-PadC27)") (class "Default")
      (node (ref "FCT_con1") (pin "C27") (pinfunction "C27_C27") (pintype "passive"))
    )
    (net (code "180") (name "unconnected-(FCT_con1-PadC35)") (class "Default")
      (node (ref "FCT_con1") (pin "C35") (pinfunction "C35_C35") (pintype "passive"))
    )
    (net (code "181") (name "unconnected-(FCT_con1-PadC37)") (class "Default")
      (node (ref "FCT_con1") (pin "C37") (pinfunction "C37_C37") (pintype "passive"))
    )
    (net (code "182") (name "unconnected-(FCT_con1-PadD4)") (class "Default")
      (node (ref "FCT_con1") (pin "D4") (pinfunction "D4_D4") (pintype "passive"))
    )
    (net (code "183") (name "unconnected-(FCT_con1-PadD5)") (class "Default")
      (node (ref "FCT_con1") (pin "D5") (pinfunction "D5_D5") (pintype "passive"))
    )
    (net (code "184") (name "unconnected-(FCT_con1-PadD8)") (class "Default")
      (node (ref "FCT_con1") (pin "D8") (pinfunction "D8_D8") (pintype "passive"))
    )
    (net (code "185") (name "unconnected-(FCT_con1-PadD9)") (class "Default")
      (node (ref "FCT_con1") (pin "D9") (pinfunction "D9_D9") (pintype "passive"))
    )
    (net (code "186") (name "unconnected-(FCT_con1-PadD26)") (class "Default")
      (node (ref "FCT_con1") (pin "D26") (pinfunction "D26_D26") (pintype "passive"))
    )
    (net (code "187") (name "unconnected-(FCT_con1-PadD27)") (class "Default")
      (node (ref "FCT_con1") (pin "D27") (pinfunction "D27_D27") (pintype "passive"))
    )
    (net (code "188") (name "unconnected-(FCT_con1-PadD29)") (class "Default")
      (node (ref "FCT_con1") (pin "D29") (pinfunction "D29_D29") (pintype "passive"))
    )
    (net (code "189") (name "unconnected-(FCT_con1-PadD30)") (class "Default")
      (node (ref "FCT_con1") (pin "D30") (pinfunction "D30_D30") (pintype "passive"))
    )
    (net (code "190") (name "unconnected-(FCT_con1-PadD31)") (class "Default")
      (node (ref "FCT_con1") (pin "D31") (pinfunction "D31_D31") (pintype "passive"))
    )
    (net (code "191") (name "unconnected-(FCT_con1-PadD33)") (class "Default")
      (node (ref "FCT_con1") (pin "D33") (pinfunction "D33_D33") (pintype "passive"))
    )
    (net (code "192") (name "unconnected-(FCT_con1-PadE2)") (class "Default")
      (node (ref "FCT_con1") (pin "E2") (pinfunction "E2_E2") (pintype "passive"))
    )
    (net (code "193") (name "unconnected-(FCT_con1-PadE3)") (class "Default")
      (node (ref "FCT_con1") (pin "E3") (pinfunction "E3_E3") (pintype "passive"))
    )
    (net (code "194") (name "unconnected-(FCT_con1-PadE9)") (class "Default")
      (node (ref "FCT_con1") (pin "E9") (pinfunction "E9_E9") (pintype "passive"))
    )
    (net (code "195") (name "unconnected-(FCT_con1-PadE10)") (class "Default")
      (node (ref "FCT_con1") (pin "E10") (pinfunction "E10_E10") (pintype "passive"))
    )
    (net (code "196") (name "unconnected-(FCT_con1-PadE24)") (class "Default")
      (node (ref "FCT_con1") (pin "E24") (pinfunction "E24_E24") (pintype "passive"))
    )
    (net (code "197") (name "unconnected-(FCT_con1-PadE25)") (class "Default")
      (node (ref "FCT_con1") (pin "E25") (pinfunction "E25_E25") (pintype "passive"))
    )
    (net (code "198") (name "unconnected-(FCT_con1-PadE27)") (class "Default")
      (node (ref "FCT_con1") (pin "E27") (pinfunction "E27_E27") (pintype "passive"))
    )
    (net (code "199") (name "unconnected-(FCT_con1-PadE28)") (class "Default")
      (node (ref "FCT_con1") (pin "E28") (pinfunction "E28_E28") (pintype "passive"))
    )
    (net (code "200") (name "unconnected-(FCT_con1-PadE30)") (class "Default")
      (node (ref "FCT_con1") (pin "E30") (pinfunction "E30_E30") (pintype "passive"))
    )
    (net (code "201") (name "unconnected-(FCT_con1-PadE31)") (class "Default")
      (node (ref "FCT_con1") (pin "E31") (pinfunction "E31_E31") (pintype "passive"))
    )
    (net (code "202") (name "unconnected-(FCT_con1-PadF4)") (class "Default")
      (node (ref "FCT_con1") (pin "F4") (pinfunction "F4_F4") (pintype "passive"))
    )
    (net (code "203") (name "unconnected-(FCT_con1-PadF5)") (class "Default")
      (node (ref "FCT_con1") (pin "F5") (pinfunction "F5_F5") (pintype "passive"))
    )
    (net (code "204") (name "unconnected-(FCT_con1-PadF25)") (class "Default")
      (node (ref "FCT_con1") (pin "F25") (pinfunction "F25_F25") (pintype "passive"))
    )
    (net (code "205") (name "unconnected-(FCT_con1-PadF26)") (class "Default")
      (node (ref "FCT_con1") (pin "F26") (pinfunction "F26_F26") (pintype "passive"))
    )
    (net (code "206") (name "unconnected-(FCT_con1-PadF28)") (class "Default")
      (node (ref "FCT_con1") (pin "F28") (pinfunction "F28_F28") (pintype "passive"))
    )
    (net (code "207") (name "unconnected-(FCT_con1-PadF29)") (class "Default")
      (node (ref "FCT_con1") (pin "F29") (pinfunction "F29_F29") (pintype "passive"))
    )
    (net (code "208") (name "unconnected-(FCT_con1-PadG2)") (class "Default")
      (node (ref "FCT_con1") (pin "G2") (pinfunction "G2_G2") (pintype "passive"))
    )
    (net (code "209") (name "unconnected-(FCT_con1-PadG3)") (class "Default")
      (node (ref "FCT_con1") (pin "G3") (pinfunction "G3_G3") (pintype "passive"))
    )
    (net (code "210") (name "unconnected-(FCT_con1-PadG6)") (class "Default")
      (node (ref "FCT_con1") (pin "G6") (pinfunction "G6_G6") (pintype "passive"))
    )
    (net (code "211") (name "unconnected-(FCT_con1-PadG7)") (class "Default")
      (node (ref "FCT_con1") (pin "G7") (pinfunction "G7_G7") (pintype "passive"))
    )
    (net (code "212") (name "unconnected-(FCT_con1-PadG9)") (class "Default")
      (node (ref "FCT_con1") (pin "G9") (pinfunction "G9_G9") (pintype "passive"))
    )
    (net (code "213") (name "unconnected-(FCT_con1-PadG10)") (class "Default")
      (node (ref "FCT_con1") (pin "G10") (pinfunction "G10_G10") (pintype "passive"))
    )
    (net (code "214") (name "unconnected-(FCT_con1-PadG27)") (class "Default")
      (node (ref "FCT_con1") (pin "G27") (pinfunction "G27_G27") (pintype "passive"))
    )
    (net (code "215") (name "unconnected-(FCT_con1-PadG28)") (class "Default")
      (node (ref "FCT_con1") (pin "G28") (pinfunction "G28_G28") (pintype "passive"))
    )
    (net (code "216") (name "unconnected-(FCT_con1-PadH1)") (class "Default")
      (node (ref "FCT_con1") (pin "H1") (pinfunction "H1_H1") (pintype "passive"))
    )
    (net (code "217") (name "unconnected-(FCT_con1-PadH2)") (class "Default")
      (node (ref "FCT_con1") (pin "H2") (pinfunction "H2_H2") (pintype "passive"))
    )
    (net (code "218") (name "unconnected-(FCT_con1-PadH4)") (class "Default")
      (node (ref "FCT_con1") (pin "H4") (pinfunction "H4_H4") (pintype "passive"))
    )
    (net (code "219") (name "unconnected-(FCT_con1-PadH5)") (class "Default")
      (node (ref "FCT_con1") (pin "H5") (pinfunction "H5_H5") (pintype "passive"))
    )
    (net (code "220") (name "unconnected-(FCT_con1-PadH7)") (class "Default")
      (node (ref "FCT_con1") (pin "H7") (pinfunction "H7_H7") (pintype "passive"))
    )
    (net (code "221") (name "unconnected-(FCT_con1-PadH8)") (class "Default")
      (node (ref "FCT_con1") (pin "H8") (pinfunction "H8_H8") (pintype "passive"))
    )
    (net (code "222") (name "unconnected-(FCT_con1-PadH10)") (class "Default")
      (node (ref "FCT_con1") (pin "H10") (pinfunction "H10_H10") (pintype "passive"))
    )
    (net (code "223") (name "unconnected-(FCT_con1-PadH11)") (class "Default")
      (node (ref "FCT_con1") (pin "H11") (pinfunction "H11_H11") (pintype "passive"))
    )
    (net (code "224") (name "unconnected-(FCT_con1-PadJ20)") (class "Default")
      (node (ref "FCT_con1") (pin "J20") (pinfunction "J20_J20") (pintype "passive"))
    )
    (net (code "225") (name "unconnected-(FCT_con1-PadJ24)") (class "Default")
      (node (ref "FCT_con1") (pin "J24") (pinfunction "J24_J24") (pintype "passive"))
    )
    (net (code "226") (name "unconnected-(FCT_con1-PadJ25)") (class "Default")
      (node (ref "FCT_con1") (pin "J25") (pinfunction "J25_J25") (pintype "passive"))
    )
    (net (code "227") (name "unconnected-(FCT_con1-PadJ27)") (class "Default")
      (node (ref "FCT_con1") (pin "J27") (pinfunction "J27_J27") (pintype "passive"))
    )
    (net (code "228") (name "unconnected-(FCT_con1-PadJ28)") (class "Default")
      (node (ref "FCT_con1") (pin "J28") (pinfunction "J28_J28") (pintype "passive"))
    )
    (net (code "229") (name "unconnected-(FCT_con1-PadJ39)") (class "Default")
      (node (ref "FCT_con1") (pin "J39") (pinfunction "J39_J39") (pintype "passive"))
    )
    (net (code "230") (name "unconnected-(FCT_con1-PadK1)") (class "Default")
      (node (ref "FCT_con1") (pin "K1") (pinfunction "K1_K1") (pintype "passive"))
    )
    (net (code "231") (name "unconnected-(FCT_con1-PadK4)") (class "Default")
      (node (ref "FCT_con1") (pin "K4") (pinfunction "K4_K4") (pintype "passive"))
    )
    (net (code "232") (name "unconnected-(FCT_con1-PadK5)") (class "Default")
      (node (ref "FCT_con1") (pin "K5") (pinfunction "K5_K5") (pintype "passive"))
    )
    (net (code "233") (name "unconnected-(FCT_con1-PadK31)") (class "Default")
      (node (ref "FCT_con1") (pin "K31") (pinfunction "K31_K31") (pintype "passive"))
    )
    (net (code "234") (name "unconnected-(FCT_con1-PadK32)") (class "Default")
      (node (ref "FCT_con1") (pin "K32") (pinfunction "K32_K32") (pintype "passive"))
    )
    (net (code "235") (name "unconnected-(FCT_con1-PadK40)") (class "Default")
      (node (ref "FCT_con1") (pin "K40") (pinfunction "K40_K40") (pintype "passive"))
    )
  )
)
